# homegreen_node_basic_v1_4_3.net
KiCad netlist of a schematic drawn in EAGLE
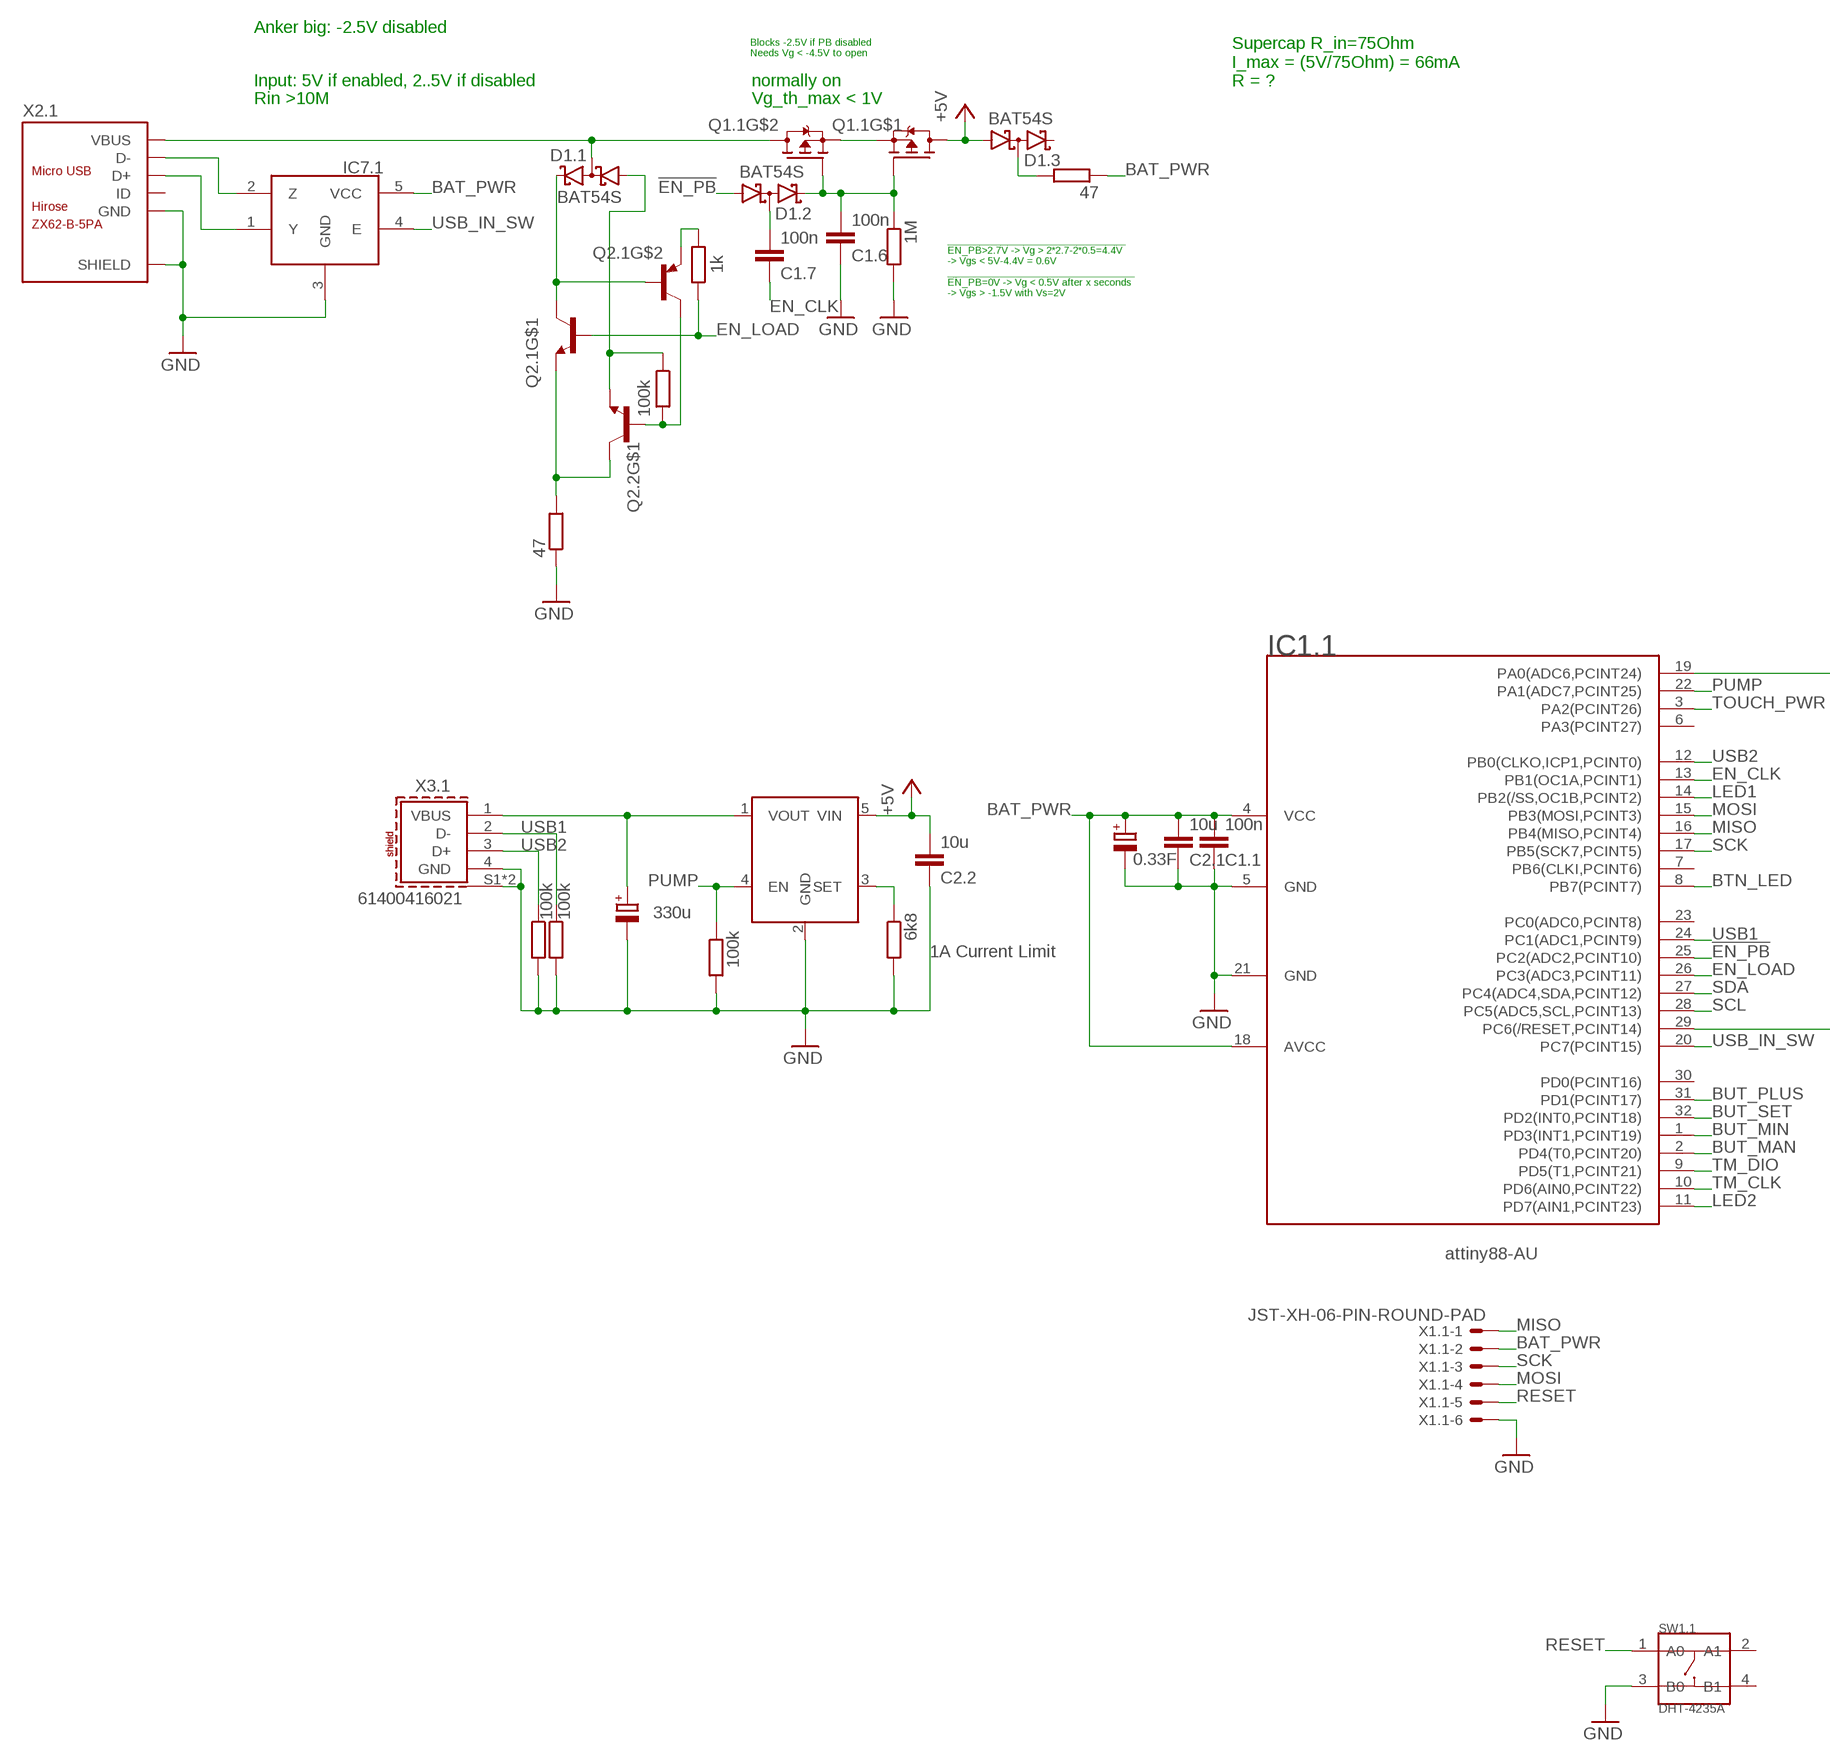
[diagram p0: schematic, sheet 1, part 1 of 2]
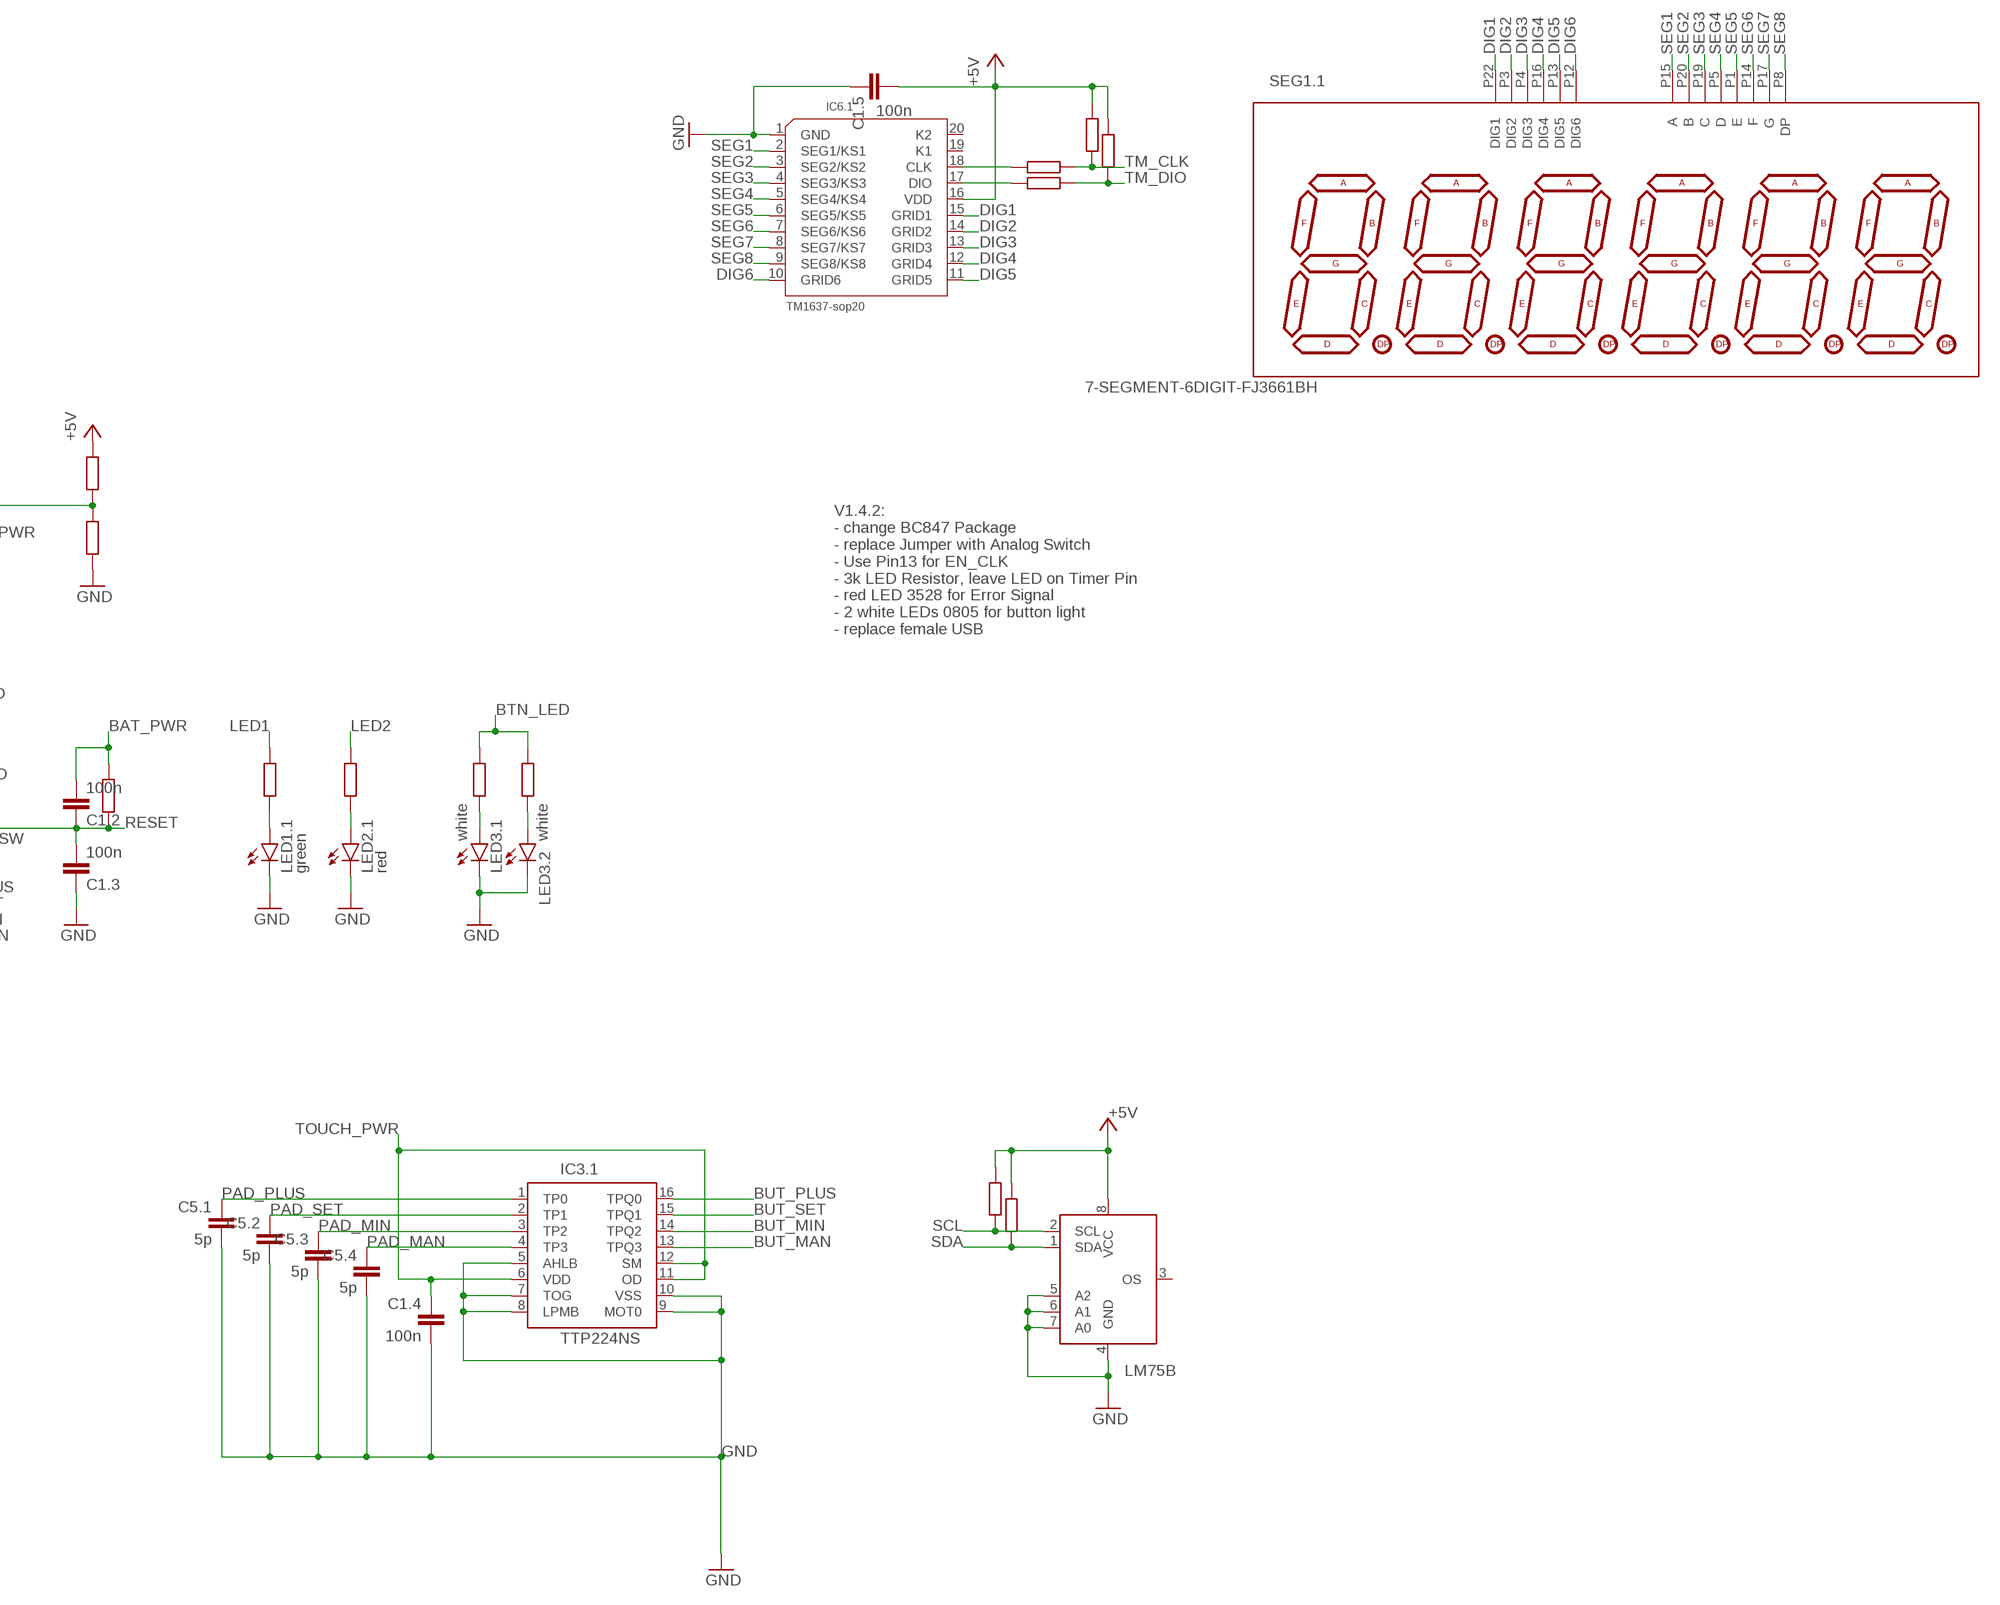
[diagram p1: schematic, sheet 1, part 2 of 2]

(export (version "E")
  (design (tool "Eeschema 10.0.6"))
  (components
    (comp (ref "C1.1")
      (value "100n")
      (footprint "eagle-import:C0805")
      (libsource (lib "eagle-import") (part "C-EUC0805"))
    )
    (comp (ref "C1.2")
      (value "100n")
      (footprint "eagle-import:C0805")
      (libsource (lib "eagle-import") (part "C-EUC0805"))
    )
    (comp (ref "C1.3")
      (value "100n")
      (footprint "eagle-import:C0805")
      (libsource (lib "eagle-import") (part "C-EUC0805"))
    )
    (comp (ref "C1.4")
      (value "100n")
      (footprint "eagle-import:C0805")
      (libsource (lib "eagle-import") (part "C-EUC0805"))
    )
    (comp (ref "C1.5")
      (value "100n")
      (footprint "eagle-import:C0805")
      (libsource (lib "eagle-import") (part "C-EUC0805"))
    )
    (comp (ref "C1.6")
      (value "100n")
      (footprint "eagle-import:C0805")
      (libsource (lib "eagle-import") (part "C-EUC0805"))
    )
    (comp (ref "C1.7")
      (value "100n")
      (footprint "eagle-import:C0805")
      (libsource (lib "eagle-import") (part "C-EUC0805"))
    )
    (comp (ref "C2.1")
      (value "10u")
      (footprint "eagle-import:C0805")
      (libsource (lib "eagle-import") (part "C-EUC0805"))
    )
    (comp (ref "C2.2")
      (value "10u")
      (footprint "eagle-import:C0805")
      (libsource (lib "eagle-import") (part "C-EUC0805"))
    )
    (comp (ref "C3.1")
      (value "0.33F")
      (footprint "eagle-import:C_FYD0H104ZF")
      (libsource (lib "eagle-import") (part "SUPERCAP"))
    )
    (comp (ref "C4.1")
      (value "330u")
      (footprint "eagle-import:PANASONIC_D")
      (libsource (lib "eagle-import") (part "CPOL-EUD"))
    )
    (comp (ref "C5.1")
      (value "5p")
      (footprint "eagle-import:C0805")
      (libsource (lib "eagle-import") (part "C-EUC0805"))
    )
    (comp (ref "C5.2")
      (value "5p")
      (footprint "eagle-import:C0805")
      (libsource (lib "eagle-import") (part "C-EUC0805"))
    )
    (comp (ref "C5.3")
      (value "5p")
      (footprint "eagle-import:C0805")
      (libsource (lib "eagle-import") (part "C-EUC0805"))
    )
    (comp (ref "C5.4")
      (value "5p")
      (footprint "eagle-import:C0805")
      (libsource (lib "eagle-import") (part "C-EUC0805"))
    )
    (comp (ref "D1.1")
      (value "BAT54S")
      (footprint "eagle-import:SOT23")
      (libsource (lib "eagle-import") (part "BAT54S"))
    )
    (comp (ref "D1.2")
      (value "BAT54S")
      (footprint "eagle-import:SOT23")
      (libsource (lib "eagle-import") (part "BAT54S"))
    )
    (comp (ref "D1.3")
      (value "BAT54S")
      (footprint "eagle-import:SOT23")
      (libsource (lib "eagle-import") (part "BAT54S"))
    )
    (comp (ref "IC1.1")
      (value "attiny88-AU")
      (footprint "eagle-import:TQFP32-08")
      (libsource (lib "eagle-import") (part "ATTINY88"))
    )
    (comp (ref "IC2.1")
      (value "LM75B")
      (footprint "eagle-import:SO8")
      (libsource (lib "eagle-import") (part "LM75B"))
    )
    (comp (ref "IC3.1")
      (value "TTP224NS")
      (footprint "eagle-import:SSOP16")
      (libsource (lib "eagle-import") (part "TTP224NS"))
    )
    (comp (ref "IC5.1")
      (value "MT9700_WS4603")
      (footprint "eagle-import:SOT23-5")
      (libsource (lib "eagle-import") (part "MT9700MT9700"))
    )
    (comp (ref "IC6.1")
      (value "TM1637-sop20")
      (footprint "eagle-import:SOP20-1.27-12.7X7.65MM")
      (fields (field (name "MPN") "TM1637"))
      (libsource (lib "eagle-import") (part "DRIVER-TM1637(SOP20)"))
    )
    (comp (ref "IC7.1")
      (value "74AHC1G66")
      (footprint "eagle-import:SOT65P212X110-5N")
      (libsource (lib "eagle-import") (part "74AHC1G66"))
    )
    (comp (ref "LED1.1")
      (value "green")
      (footprint "eagle-import:KA-3528ASYC")
      (libsource (lib "eagle-import") (part "LEDKA-3528ASYC"))
    )
    (comp (ref "LED2.1")
      (value "red")
      (footprint "eagle-import:KA-3528ASYC")
      (libsource (lib "eagle-import") (part "LEDKA-3528ASYC"))
    )
    (comp (ref "LED3.1")
      (value "white")
      (footprint "eagle-import:CHIPLED_0805")
      (libsource (lib "eagle-import") (part "LEDCHIPLED_0805"))
    )
    (comp (ref "LED3.2")
      (value "white")
      (footprint "eagle-import:CHIPLED_0805")
      (libsource (lib "eagle-import") (part "LEDCHIPLED_0805"))
    )
    (comp (ref "Q1.1")
      (value "WST2011")
      (footprint "eagle-import:SOT23-6")
      (libsource (lib "eagle-import") (part "CJL2623SOT23-6"))
    )
    (comp (ref "Q2.1")
      (value "BC817DPN")
      (footprint "eagle-import:SOT23-6")
      (libsource (lib "eagle-import") (part "BC817DPN"))
    )
    (comp (ref "Q2.2")
      (value "BC817DPN")
      (footprint "eagle-import:SOT23-6")
      (libsource (lib "eagle-import") (part "BC817DPN"))
    )
    (comp (ref "R1.1")
      (value "6k8")
      (footprint "eagle-import:R0805")
      (libsource (lib "eagle-import") (part "R-EU_R0805"))
    )
    (comp (ref "R1.2")
      (value "6k8")
      (footprint "eagle-import:R0805")
      (libsource (lib "eagle-import") (part "R-EU_R0805"))
    )
    (comp (ref "R1.3")
      (value "6k8")
      (footprint "eagle-import:R0805")
      (libsource (lib "eagle-import") (part "R-EU_R0805"))
    )
    (comp (ref "R2.1")
      (value "1k")
      (footprint "eagle-import:R0805")
      (libsource (lib "eagle-import") (part "R-EU_R0805"))
    )
    (comp (ref "R2.2")
      (value "1k")
      (footprint "eagle-import:R0805")
      (libsource (lib "eagle-import") (part "R-EU_R0805"))
    )
    (comp (ref "R2.3")
      (value "1k")
      (footprint "eagle-import:R0805")
      (libsource (lib "eagle-import") (part "R-EU_R0805"))
    )
    (comp (ref "R2.4")
      (value "1k")
      (footprint "eagle-import:R0805")
      (libsource (lib "eagle-import") (part "R-EU_R0805"))
    )
    (comp (ref "R2.5")
      (value "1k")
      (footprint "eagle-import:R0805")
      (libsource (lib "eagle-import") (part "R-EU_R0805"))
    )
    (comp (ref "R3.1")
      (value "47")
      (footprint "eagle-import:R0805")
      (libsource (lib "eagle-import") (part "R-EU_R0805"))
    )
    (comp (ref "R3.2")
      (value "47")
      (footprint "eagle-import:R0805")
      (libsource (lib "eagle-import") (part "R-EU_R0805"))
    )
    (comp (ref "R4.1")
      (value "3k")
      (footprint "eagle-import:R0805")
      (libsource (lib "eagle-import") (part "R-EU_R0805"))
    )
    (comp (ref "R4.2")
      (value "3k")
      (footprint "eagle-import:R0805")
      (libsource (lib "eagle-import") (part "R-EU_R0805"))
    )
    (comp (ref "R5.1")
      (value "100k")
      (footprint "eagle-import:R0805")
      (libsource (lib "eagle-import") (part "R-EU_R0805"))
    )
    (comp (ref "R5.2")
      (value "100k")
      (footprint "eagle-import:R0805")
      (libsource (lib "eagle-import") (part "R-EU_R0805"))
    )
    (comp (ref "R5.3")
      (value "100k")
      (footprint "eagle-import:R0805")
      (libsource (lib "eagle-import") (part "R-EU_R0805"))
    )
    (comp (ref "R5.4")
      (value "100k")
      (footprint "eagle-import:R0805")
      (libsource (lib "eagle-import") (part "R-EU_R0805"))
    )
    (comp (ref "R5.5")
      (value "100k")
      (footprint "eagle-import:R0805")
      (libsource (lib "eagle-import") (part "R-EU_R0805"))
    )
    (comp (ref "R5.6")
      (value "100k")
      (footprint "eagle-import:R0805")
      (libsource (lib "eagle-import") (part "R-EU_R0805"))
    )
    (comp (ref "R5.7")
      (value "100k")
      (footprint "eagle-import:R0805")
      (libsource (lib "eagle-import") (part "R-EU_R0805"))
    )
    (comp (ref "R5.8")
      (value "100k")
      (footprint "eagle-import:R0805")
      (libsource (lib "eagle-import") (part "R-EU_R0805"))
    )
    (comp (ref "R5.9")
      (value "100k")
      (footprint "eagle-import:R0805")
      (libsource (lib "eagle-import") (part "R-EU_R0805"))
    )
    (comp (ref "R6.1")
      (value "1M")
      (footprint "eagle-import:R0805")
      (libsource (lib "eagle-import") (part "R-EU_R0805"))
    )
    (comp (ref "SEG1.1")
      (value "7-SEGMENT-6DIGIT-FJ3661BH")
      (footprint "eagle-import:7SEG_6D_FJ3661BH")
      (libsource (lib "eagle-import") (part "7-SEGMENT-6DIGIT-FJ3661BH"))
    )
    (comp (ref "SW1.1")
      (value "DHT-4235A")
      (footprint "eagle-import:SW4-SMD-4.2X3.2X2.5MM")
      (libsource (lib "eagle-import") (part "SMD-BUTTON-TOP-DHT-4235A(4P-4.2X3.2MM)"))
    )
    (comp (ref "X1.1")
      (value "JST-XH-06-PIN-ROUND-PAD")
      (footprint "eagle-import:JST-XH-06-PACKAGE-ROUND-PAD")
      (libsource (lib "eagle-import") (part "JST-XH-06-PIN-ROUND-PAD"))
    )
    (comp (ref "X2.1")
      (value "ZX62-B-5PA")
      (footprint "eagle-import:ZX62-B-5PA")
      (libsource (lib "eagle-import") (part "MICRO-USB-SMD(ZX62-B-5PA)"))
    )
    (comp (ref "X3.1")
      (value "61400416021")
      (footprint "eagle-import:61400416021")
      (libsource (lib "eagle-import") (part "61400416021"))
    )
  )
  (nets
    (net (code "1") (name "+5V") (class "Default")
      (node (ref "C1.5") (pin "2") (pinfunction "2_2") (pintype "passive"))
      (node (ref "C2.2") (pin "2") (pinfunction "2_2") (pintype "passive"))
      (node (ref "D1.3") (pin "1") (pinfunction "A1_1") (pintype "passive"))
      (node (ref "IC2.1") (pin "8") (pinfunction "VCC_8") (pintype "power_in"))
      (node (ref "IC5.1") (pin "5") (pinfunction "VIN_5") (pintype "bidirectional"))
      (node (ref "IC6.1") (pin "16") (pinfunction "VDD_16") (pintype "bidirectional"))
      (node (ref "Q1.1") (pin "6") (pinfunction "D_6") (pintype "passive"))
      (node (ref "R1.1") (pin "2") (pinfunction "2_2") (pintype "passive"))
      (node (ref "R1.3") (pin "2") (pinfunction "2_2") (pintype "passive"))
      (node (ref "R5.3") (pin "1") (pinfunction "1_1") (pintype "passive"))
      (node (ref "R5.5") (pin "2") (pinfunction "2_2") (pintype "passive"))
      (node (ref "R5.6") (pin "2") (pinfunction "2_2") (pintype "passive"))
    )
    (net (code "2") (name "/BAT_PWR") (class "Default")
      (node (ref "C1.1") (pin "2") (pinfunction "2_2") (pintype "passive"))
      (node (ref "C1.2") (pin "2") (pinfunction "2_2") (pintype "passive"))
      (node (ref "C2.1") (pin "2") (pinfunction "2_2") (pintype "passive"))
      (node (ref "C3.1") (pin "+") (pinfunction "+_+") (pintype "passive"))
      (node (ref "IC1.1") (pin "18") (pinfunction "AVCC_18") (pintype "power_in"))
      (node (ref "IC1.1") (pin "4") (pinfunction "VCC_4") (pintype "power_in"))
      (node (ref "IC7.1") (pin "5") (pinfunction "VCC_5") (pintype "bidirectional"))
      (node (ref "R3.2") (pin "1") (pinfunction "1_1") (pintype "passive"))
      (node (ref "R5.7") (pin "1") (pinfunction "1_1") (pintype "passive"))
      (node (ref "X1.1") (pin "2") (pinfunction "S_2") (pintype "passive"))
    )
    (net (code "3") (name "/BTN_LED") (class "Default")
      (node (ref "IC1.1") (pin "8") (pinfunction "PB7(PCINT7)_8") (pintype "bidirectional"))
      (node (ref "R2.1") (pin "2") (pinfunction "2_2") (pintype "passive"))
      (node (ref "R2.5") (pin "2") (pinfunction "2_2") (pintype "passive"))
    )
    (net (code "4") (name "/BUT_MAN") (class "Default")
      (node (ref "IC1.1") (pin "2") (pinfunction "PD4(T0,PCINT20)_2") (pintype "bidirectional"))
      (node (ref "IC3.1") (pin "13") (pinfunction "TPQ3_13") (pintype "bidirectional"))
    )
    (net (code "5") (name "/BUT_MIN") (class "Default")
      (node (ref "IC1.1") (pin "1") (pinfunction "PD3(INT1,PCINT19)_1") (pintype "bidirectional"))
      (node (ref "IC3.1") (pin "14") (pinfunction "TPQ2_14") (pintype "bidirectional"))
    )
    (net (code "6") (name "/BUT_PLUS") (class "Default")
      (node (ref "IC1.1") (pin "31") (pinfunction "PD1(PCINT17)_31") (pintype "bidirectional"))
      (node (ref "IC3.1") (pin "16") (pinfunction "TPQ0_16") (pintype "bidirectional"))
    )
    (net (code "7") (name "/BUT_SET") (class "Default")
      (node (ref "IC1.1") (pin "32") (pinfunction "PD2(INT0,PCINT18)_32") (pintype "bidirectional"))
      (node (ref "IC3.1") (pin "15") (pinfunction "TPQ1_15") (pintype "bidirectional"))
    )
    (net (code "8") (name "/DIG1") (class "Default")
      (node (ref "IC6.1") (pin "15") (pinfunction "GRID1_15") (pintype "bidirectional"))
      (node (ref "SEG1.1") (pin "P22") (pinfunction "DIG1_P22") (pintype "bidirectional"))
    )
    (net (code "9") (name "/DIG2") (class "Default")
      (node (ref "IC6.1") (pin "14") (pinfunction "GRID2_14") (pintype "bidirectional"))
      (node (ref "SEG1.1") (pin "P3") (pinfunction "DIG2_P3") (pintype "bidirectional"))
    )
    (net (code "10") (name "/DIG3") (class "Default")
      (node (ref "IC6.1") (pin "13") (pinfunction "GRID3_13") (pintype "bidirectional"))
      (node (ref "SEG1.1") (pin "P4") (pinfunction "DIG3_P4") (pintype "bidirectional"))
    )
    (net (code "11") (name "/DIG4") (class "Default")
      (node (ref "IC6.1") (pin "12") (pinfunction "GRID4_12") (pintype "bidirectional"))
      (node (ref "SEG1.1") (pin "P16") (pinfunction "DIG4_P16") (pintype "bidirectional"))
    )
    (net (code "12") (name "/DIG5") (class "Default")
      (node (ref "IC6.1") (pin "11") (pinfunction "GRID5_11") (pintype "bidirectional"))
      (node (ref "SEG1.1") (pin "P13") (pinfunction "DIG5_P13") (pintype "bidirectional"))
    )
    (net (code "13") (name "/DIG6") (class "Default")
      (node (ref "IC6.1") (pin "10") (pinfunction "GRID6_10") (pintype "bidirectional"))
      (node (ref "SEG1.1") (pin "P12") (pinfunction "DIG6_P12") (pintype "bidirectional"))
    )
    (net (code "14") (name "/EN_CLK") (class "Default")
      (node (ref "C1.7") (pin "1") (pinfunction "1_1") (pintype "passive"))
      (node (ref "IC1.1") (pin "13") (pinfunction "PB1(OC1A,PCINT1)_13") (pintype "bidirectional"))
    )
    (net (code "15") (name "/EN_LOAD") (class "Default")
      (node (ref "IC1.1") (pin "26") (pinfunction "PC3(ADC3,PCINT11)_26") (pintype "bidirectional"))
      (node (ref "Q2.1") (pin "2") (pinfunction "B_2") (pintype "passive"))
      (node (ref "R2.4") (pin "1") (pinfunction "1_1") (pintype "passive"))
    )
    (net (code "16") (name "/LED1") (class "Default")
      (node (ref "IC1.1") (pin "14") (pinfunction "PB2(/SS,OC1B,PCINT2)_14") (pintype "bidirectional"))
      (node (ref "R4.1") (pin "2") (pinfunction "2_2") (pintype "passive"))
    )
    (net (code "17") (name "/LED2") (class "Default")
      (node (ref "IC1.1") (pin "11") (pinfunction "PD7(AIN1,PCINT23)_11") (pintype "bidirectional"))
      (node (ref "R4.2") (pin "2") (pinfunction "2_2") (pintype "passive"))
    )
    (net (code "18") (name "/MISO") (class "Default")
      (node (ref "IC1.1") (pin "16") (pinfunction "PB4(MISO,PCINT4)_16") (pintype "bidirectional"))
      (node (ref "X1.1") (pin "1") (pinfunction "S_1") (pintype "passive"))
    )
    (net (code "19") (name "/MOSI") (class "Default")
      (node (ref "IC1.1") (pin "15") (pinfunction "PB3(MOSI,PCINT3)_15") (pintype "bidirectional"))
      (node (ref "X1.1") (pin "4") (pinfunction "S_4") (pintype "passive"))
    )
    (net (code "20") (name "/PAD_MAN") (class "Default")
      (node (ref "C5.4") (pin "1") (pinfunction "1_1") (pintype "passive"))
      (node (ref "IC3.1") (pin "4") (pinfunction "TP3_4") (pintype "bidirectional"))
    )
    (net (code "21") (name "/PAD_MIN") (class "Default")
      (node (ref "C5.3") (pin "1") (pinfunction "1_1") (pintype "passive"))
      (node (ref "IC3.1") (pin "3") (pinfunction "TP2_3") (pintype "bidirectional"))
    )
    (net (code "22") (name "/PAD_PLUS") (class "Default")
      (node (ref "C5.1") (pin "1") (pinfunction "1_1") (pintype "passive"))
      (node (ref "IC3.1") (pin "1") (pinfunction "TP0_1") (pintype "bidirectional"))
    )
    (net (code "23") (name "/PAD_SET") (class "Default")
      (node (ref "C5.2") (pin "1") (pinfunction "1_1") (pintype "passive"))
      (node (ref "IC3.1") (pin "2") (pinfunction "TP1_2") (pintype "bidirectional"))
    )
    (net (code "24") (name "/PUMP") (class "Default")
      (node (ref "IC1.1") (pin "22") (pinfunction "PA1(ADC7,PCINT25)_22") (pintype "bidirectional"))
      (node (ref "IC5.1") (pin "4") (pinfunction "EN_4") (pintype "bidirectional"))
      (node (ref "R5.2") (pin "1") (pinfunction "1_1") (pintype "passive"))
    )
    (net (code "25") (name "/RESET") (class "Default")
      (node (ref "C1.2") (pin "1") (pinfunction "1_1") (pintype "passive"))
      (node (ref "C1.3") (pin "2") (pinfunction "2_2") (pintype "passive"))
      (node (ref "IC1.1") (pin "29") (pinfunction "PC6(/RESET,PCINT14)_29") (pintype "bidirectional"))
      (node (ref "R5.7") (pin "2") (pinfunction "2_2") (pintype "passive"))
      (node (ref "SW1.1") (pin "1") (pinfunction "A0_1") (pintype "bidirectional"))
      (node (ref "X1.1") (pin "5") (pinfunction "S_5") (pintype "passive"))
    )
    (net (code "26") (name "/SCK") (class "Default")
      (node (ref "IC1.1") (pin "17") (pinfunction "PB5(SCK7,PCINT5)_17") (pintype "bidirectional"))
      (node (ref "X1.1") (pin "3") (pinfunction "S_3") (pintype "passive"))
    )
    (net (code "27") (name "/SCL") (class "Default")
      (node (ref "IC1.1") (pin "28") (pinfunction "PC5(ADC5,SCL,PCINT13)_28") (pintype "bidirectional"))
      (node (ref "IC2.1") (pin "2") (pinfunction "SCL_2") (pintype "bidirectional"))
      (node (ref "R1.3") (pin "1") (pinfunction "1_1") (pintype "passive"))
    )
    (net (code "28") (name "/SDA") (class "Default")
      (node (ref "IC1.1") (pin "27") (pinfunction "PC4(ADC4,SDA,PCINT12)_27") (pintype "bidirectional"))
      (node (ref "IC2.1") (pin "1") (pinfunction "SDA_1") (pintype "bidirectional"))
      (node (ref "R1.1") (pin "1") (pinfunction "1_1") (pintype "passive"))
    )
    (net (code "29") (name "/SEG1") (class "Default")
      (node (ref "IC6.1") (pin "2") (pinfunction "SEG1/KS1_2") (pintype "bidirectional"))
      (node (ref "SEG1.1") (pin "P15") (pinfunction "A_P15") (pintype "bidirectional"))
    )
    (net (code "30") (name "/SEG2") (class "Default")
      (node (ref "IC6.1") (pin "3") (pinfunction "SEG2/KS2_3") (pintype "bidirectional"))
      (node (ref "SEG1.1") (pin "P20") (pinfunction "B_P20") (pintype "bidirectional"))
    )
    (net (code "31") (name "/SEG3") (class "Default")
      (node (ref "IC6.1") (pin "4") (pinfunction "SEG3/KS3_4") (pintype "bidirectional"))
      (node (ref "SEG1.1") (pin "P19") (pinfunction "C_P19") (pintype "bidirectional"))
    )
    (net (code "32") (name "/SEG4") (class "Default")
      (node (ref "IC6.1") (pin "5") (pinfunction "SEG4/KS4_5") (pintype "bidirectional"))
      (node (ref "SEG1.1") (pin "P5") (pinfunction "D_P5") (pintype "bidirectional"))
    )
    (net (code "33") (name "/SEG5") (class "Default")
      (node (ref "IC6.1") (pin "6") (pinfunction "SEG5/KS5_6") (pintype "bidirectional"))
      (node (ref "SEG1.1") (pin "P1") (pinfunction "E_P1") (pintype "bidirectional"))
    )
    (net (code "34") (name "/SEG6") (class "Default")
      (node (ref "IC6.1") (pin "7") (pinfunction "SEG6/KS6_7") (pintype "bidirectional"))
      (node (ref "SEG1.1") (pin "P14") (pinfunction "F_P14") (pintype "bidirectional"))
    )
    (net (code "35") (name "/SEG7") (class "Default")
      (node (ref "IC6.1") (pin "8") (pinfunction "SEG7/KS7_8") (pintype "bidirectional"))
      (node (ref "SEG1.1") (pin "P17") (pinfunction "G_P17") (pintype "bidirectional"))
    )
    (net (code "36") (name "/SEG8") (class "Default")
      (node (ref "IC6.1") (pin "9") (pinfunction "SEG8/KS8_9") (pintype "bidirectional"))
      (node (ref "SEG1.1") (pin "P8") (pinfunction "DP_P8") (pintype "bidirectional"))
    )
    (net (code "37") (name "/TM_CLK") (class "Default")
      (node (ref "IC1.1") (pin "10") (pinfunction "PD6(AIN0,PCINT22)_10") (pintype "bidirectional"))
      (node (ref "R2.2") (pin "1") (pinfunction "1_1") (pintype "passive"))
      (node (ref "R5.5") (pin "1") (pinfunction "1_1") (pintype "passive"))
    )
    (net (code "38") (name "/TM_DIO") (class "Default")
      (node (ref "IC1.1") (pin "9") (pinfunction "PD5(T1,PCINT21)_9") (pintype "bidirectional"))
      (node (ref "R2.3") (pin "1") (pinfunction "1_1") (pintype "passive"))
      (node (ref "R5.6") (pin "1") (pinfunction "1_1") (pintype "passive"))
    )
    (net (code "39") (name "/TOUCH_PWR") (class "Default")
      (node (ref "C1.4") (pin "1") (pinfunction "1_1") (pintype "passive"))
      (node (ref "IC1.1") (pin "3") (pinfunction "PA2(PCINT26)_3") (pintype "bidirectional"))
      (node (ref "IC3.1") (pin "11") (pinfunction "OD_11") (pintype "bidirectional"))
      (node (ref "IC3.1") (pin "12") (pinfunction "SM_12") (pintype "bidirectional"))
      (node (ref "IC3.1") (pin "6") (pinfunction "VDD_6") (pintype "power_in"))
    )
    (net (code "40") (name "/USB1") (class "Default")
      (node (ref "IC1.1") (pin "24") (pinfunction "PC1(ADC1,PCINT9)_24") (pintype "bidirectional"))
      (node (ref "R5.9") (pin "1") (pinfunction "1_1") (pintype "passive"))
      (node (ref "X3.1") (pin "2") (pinfunction "D-_2") (pintype "bidirectional"))
    )
    (net (code "41") (name "/USB2") (class "Default")
      (node (ref "IC1.1") (pin "12") (pinfunction "PB0(CLKO,ICP1,PCINT0)_12") (pintype "bidirectional"))
      (node (ref "R5.8") (pin "1") (pinfunction "1_1") (pintype "passive"))
      (node (ref "X3.1") (pin "3") (pinfunction "D+_3") (pintype "bidirectional"))
    )
    (net (code "42") (name "/USB_IN_SW") (class "Default")
      (node (ref "IC1.1") (pin "20") (pinfunction "PC7(PCINT15)_20") (pintype "bidirectional"))
      (node (ref "IC7.1") (pin "4") (pinfunction "E_4") (pintype "bidirectional"))
    )
    (net (code "43") (name "/~{EN_PB}") (class "Default")
      (node (ref "D1.2") (pin "1") (pinfunction "A1_1") (pintype "passive"))
      (node (ref "IC1.1") (pin "25") (pinfunction "PC2(ADC2,PCINT10)_25") (pintype "bidirectional"))
    )
    (net (code "44") (name "GND") (class "Default")
      (node (ref "C1.1") (pin "1") (pinfunction "1_1") (pintype "passive"))
      (node (ref "C1.3") (pin "1") (pinfunction "1_1") (pintype "passive"))
      (node (ref "C1.4") (pin "2") (pinfunction "2_2") (pintype "passive"))
      (node (ref "C1.5") (pin "1") (pinfunction "1_1") (pintype "passive"))
      (node (ref "C1.6") (pin "1") (pinfunction "1_1") (pintype "passive"))
      (node (ref "C2.1") (pin "1") (pinfunction "1_1") (pintype "passive"))
      (node (ref "C2.2") (pin "1") (pinfunction "1_1") (pintype "passive"))
      (node (ref "C3.1") (pin "-") (pinfunction "-_-") (pintype "passive"))
      (node (ref "C4.1") (pin "-") (pinfunction "-_-") (pintype "passive"))
      (node (ref "C5.1") (pin "2") (pinfunction "2_2") (pintype "passive"))
      (node (ref "C5.2") (pin "2") (pinfunction "2_2") (pintype "passive"))
      (node (ref "C5.3") (pin "2") (pinfunction "2_2") (pintype "passive"))
      (node (ref "C5.4") (pin "2") (pinfunction "2_2") (pintype "passive"))
      (node (ref "IC1.1") (pin "21") (pinfunction "GND_21") (pintype "power_in"))
      (node (ref "IC1.1") (pin "5") (pinfunction "GND_5") (pintype "power_in"))
      (node (ref "IC2.1") (pin "4") (pinfunction "GND_4") (pintype "bidirectional"))
      (node (ref "IC2.1") (pin "5") (pinfunction "A2_5") (pintype "input"))
      (node (ref "IC2.1") (pin "6") (pinfunction "A1_6") (pintype "input"))
      (node (ref "IC2.1") (pin "7") (pinfunction "A0_7") (pintype "input"))
      (node (ref "IC3.1") (pin "10") (pinfunction "VSS_10") (pintype "power_in"))
      (node (ref "IC3.1") (pin "5") (pinfunction "AHLB_5") (pintype "bidirectional"))
      (node (ref "IC3.1") (pin "7") (pinfunction "TOG_7") (pintype "bidirectional"))
      (node (ref "IC3.1") (pin "8") (pinfunction "LPMB_8") (pintype "bidirectional"))
      (node (ref "IC3.1") (pin "9") (pinfunction "MOT0_9") (pintype "bidirectional"))
      (node (ref "IC5.1") (pin "2") (pinfunction "GND_2") (pintype "bidirectional"))
      (node (ref "IC6.1") (pin "1") (pinfunction "GND_1") (pintype "bidirectional"))
      (node (ref "IC7.1") (pin "3") (pinfunction "GND_3") (pintype "bidirectional"))
      (node (ref "LED1.1") (pin "C") (pinfunction "C_C") (pintype "passive"))
      (node (ref "LED2.1") (pin "C") (pinfunction "C_C") (pintype "passive"))
      (node (ref "LED3.1") (pin "C") (pinfunction "C_C") (pintype "passive"))
      (node (ref "LED3.2") (pin "C") (pinfunction "C_C") (pintype "passive"))
      (node (ref "R1.2") (pin "2") (pinfunction "2_2") (pintype "passive"))
      (node (ref "R3.1") (pin "1") (pinfunction "1_1") (pintype "passive"))
      (node (ref "R5.2") (pin "2") (pinfunction "2_2") (pintype "passive"))
      (node (ref "R5.4") (pin "2") (pinfunction "2_2") (pintype "passive"))
      (node (ref "R5.8") (pin "2") (pinfunction "2_2") (pintype "passive"))
      (node (ref "R5.9") (pin "2") (pinfunction "2_2") (pintype "passive"))
      (node (ref "R6.1") (pin "2") (pinfunction "2_2") (pintype "passive"))
      (node (ref "SW1.1") (pin "3") (pinfunction "B0_3") (pintype "bidirectional"))
      (node (ref "X1.1") (pin "6") (pinfunction "S_6") (pintype "passive"))
      (node (ref "X2.1") (pin "5") (pinfunction "GND_5") (pintype "power_in"))
      (node (ref "X2.1") (pin "P1") (pinfunction "SHIELD_P1") (pintype "power_in"))
      (node (ref "X2.1") (pin "P2") (pinfunction "SHIELD_P2") (pintype "power_in"))
      (node (ref "X2.1") (pin "P3") (pinfunction "SHIELD_P3") (pintype "power_in"))
      (node (ref "X2.1") (pin "P4") (pinfunction "SHIELD_P4") (pintype "power_in"))
      (node (ref "X2.1") (pin "P5") (pinfunction "SHIELD_P5") (pintype "power_in"))
      (node (ref "X2.1") (pin "P6") (pinfunction "SHIELD_P6") (pintype "power_in"))
      (node (ref "X3.1") (pin "4") (pinfunction "GND_4") (pintype "bidirectional"))
      (node (ref "X3.1") (pin "S1") (pinfunction "SHIELD_S1") (pintype "bidirectional"))
      (node (ref "X3.1") (pin "S2") (pinfunction "SHIELD_S2") (pintype "bidirectional"))
    )
    (net (code "45") (name "Net-(D1.1-A1)") (class "Default")
      (node (ref "D1.1") (pin "1") (pinfunction "A1_1") (pintype "passive"))
      (node (ref "Q2.2") (pin "1") (pinfunction "E_1") (pintype "passive"))
      (node (ref "R5.1") (pin "1") (pinfunction "1_1") (pintype "passive"))
    )
    (net (code "46") (name "Net-(D1.1-C1A2)") (class "Default")
      (node (ref "D1.1") (pin "3") (pinfunction "C1A2_3") (pintype "passive"))
      (node (ref "Q1.1") (pin "4") (pinfunction "D_4") (pintype "passive"))
      (node (ref "X2.1") (pin "1") (pinfunction "VBUS_1") (pintype "power_in"))
    )
    (net (code "47") (name "Net-(D1.1-C2)") (class "Default")
      (node (ref "D1.1") (pin "2") (pinfunction "C2_2") (pintype "passive"))
      (node (ref "Q2.1") (pin "5") (pinfunction "B_5") (pintype "passive"))
      (node (ref "Q2.1") (pin "6") (pinfunction "C_6") (pintype "passive"))
    )
    (net (code "48") (name "Net-(D1.2-C1A2)") (class "Default")
      (node (ref "C1.7") (pin "2") (pinfunction "2_2") (pintype "passive"))
      (node (ref "D1.2") (pin "3") (pinfunction "C1A2_3") (pintype "passive"))
    )
    (net (code "49") (name "Net-(D1.2-C2)") (class "Default")
      (node (ref "C1.6") (pin "2") (pinfunction "2_2") (pintype "passive"))
      (node (ref "D1.2") (pin "2") (pinfunction "C2_2") (pintype "passive"))
      (node (ref "Q1.1") (pin "1") (pinfunction "G_1") (pintype "passive"))
      (node (ref "Q1.1") (pin "3") (pinfunction "G_3") (pintype "passive"))
      (node (ref "R6.1") (pin "1") (pinfunction "1_1") (pintype "passive"))
    )
    (net (code "50") (name "Net-(D1.3-C1A2)") (class "Default")
      (node (ref "D1.3") (pin "3") (pinfunction "C1A2_3") (pintype "passive"))
      (node (ref "R3.2") (pin "2") (pinfunction "2_2") (pintype "passive"))
    )
    (net (code "51") (name "Net-(IC1.1-PA0(ADC6,PCINT24))") (class "Default")
      (node (ref "IC1.1") (pin "19") (pinfunction "PA0(ADC6,PCINT24)_19") (pintype "bidirectional"))
      (node (ref "R5.3") (pin "2") (pinfunction "2_2") (pintype "passive"))
      (node (ref "R5.4") (pin "1") (pinfunction "1_1") (pintype "passive"))
    )
    (net (code "52") (name "Net-(IC5.1-SET)") (class "Default")
      (node (ref "IC5.1") (pin "3") (pinfunction "SET_3") (pintype "bidirectional"))
      (node (ref "R1.2") (pin "1") (pinfunction "1_1") (pintype "passive"))
    )
    (net (code "53") (name "Net-(IC5.1-VOUT)") (class "Default")
      (node (ref "C4.1") (pin "+") (pinfunction "+_+") (pintype "passive"))
      (node (ref "IC5.1") (pin "1") (pinfunction "VOUT_1") (pintype "bidirectional"))
      (node (ref "X3.1") (pin "1") (pinfunction "VBUS_1") (pintype "bidirectional"))
    )
    (net (code "54") (name "Net-(IC6.1-CLK)") (class "Default")
      (node (ref "IC6.1") (pin "18") (pinfunction "CLK_18") (pintype "bidirectional"))
      (node (ref "R2.2") (pin "2") (pinfunction "2_2") (pintype "passive"))
    )
    (net (code "55") (name "Net-(IC6.1-DIO)") (class "Default")
      (node (ref "IC6.1") (pin "17") (pinfunction "DIO_17") (pintype "bidirectional"))
      (node (ref "R2.3") (pin "2") (pinfunction "2_2") (pintype "passive"))
    )
    (net (code "56") (name "Net-(IC7.1-Y)") (class "Default")
      (node (ref "IC7.1") (pin "1") (pinfunction "Y_1") (pintype "bidirectional"))
      (node (ref "X2.1") (pin "3") (pinfunction "D+_3") (pintype "bidirectional"))
    )
    (net (code "57") (name "Net-(IC7.1-Z)") (class "Default")
      (node (ref "IC7.1") (pin "2") (pinfunction "Z_2") (pintype "bidirectional"))
      (node (ref "X2.1") (pin "2") (pinfunction "D-_2") (pintype "bidirectional"))
    )
    (net (code "58") (name "Net-(LED1.1-PadA)") (class "Default")
      (node (ref "LED1.1") (pin "A") (pinfunction "A_A") (pintype "passive"))
      (node (ref "R4.1") (pin "1") (pinfunction "1_1") (pintype "passive"))
    )
    (net (code "59") (name "Net-(LED2.1-PadA)") (class "Default")
      (node (ref "LED2.1") (pin "A") (pinfunction "A_A") (pintype "passive"))
      (node (ref "R4.2") (pin "1") (pinfunction "1_1") (pintype "passive"))
    )
    (net (code "60") (name "Net-(LED3.1-PadA)") (class "Default")
      (node (ref "LED3.1") (pin "A") (pinfunction "A_A") (pintype "passive"))
      (node (ref "R2.1") (pin "1") (pinfunction "1_1") (pintype "passive"))
    )
    (net (code "61") (name "Net-(LED3.2-PadA)") (class "Default")
      (node (ref "LED3.2") (pin "A") (pinfunction "A_A") (pintype "passive"))
      (node (ref "R2.5") (pin "1") (pinfunction "1_1") (pintype "passive"))
    )
    (net (code "62") (name "Net-(Q1.1A-S)") (class "Default")
      (node (ref "Q1.1") (pin "2") (pinfunction "S_2") (pintype "passive"))
      (node (ref "Q1.1") (pin "5") (pinfunction "S_5") (pintype "passive"))
    )
    (net (code "63") (name "Net-(Q2.1A-E)") (class "Default")
      (node (ref "Q2.1") (pin "1") (pinfunction "E_1") (pintype "passive"))
      (node (ref "Q2.2") (pin "6") (pinfunction "C_6") (pintype "passive"))
      (node (ref "R3.1") (pin "2") (pinfunction "2_2") (pintype "passive"))
    )
    (net (code "64") (name "Net-(Q2.1B-C)") (class "Default")
      (node (ref "Q2.1") (pin "3") (pinfunction "C_3") (pintype "passive"))
      (node (ref "Q2.2") (pin "2") (pinfunction "B_2") (pintype "passive"))
      (node (ref "R5.1") (pin "2") (pinfunction "2_2") (pintype "passive"))
    )
    (net (code "65") (name "Net-(Q2.1B-E)") (class "Default")
      (node (ref "Q2.1") (pin "4") (pinfunction "E_4") (pintype "passive"))
      (node (ref "R2.4") (pin "2") (pinfunction "2_2") (pintype "passive"))
    )
    (net (code "66") (name "unconnected-(D1.3-C2-Pad2)") (class "Default")
      (node (ref "D1.3") (pin "2") (pinfunction "C2_2") (pintype "passive"))
    )
    (net (code "67") (name "unconnected-(IC1.1-PA3(PCINT27)-Pad6)") (class "Default")
      (node (ref "IC1.1") (pin "6") (pinfunction "PA3(PCINT27)_6") (pintype "bidirectional"))
    )
    (net (code "68") (name "unconnected-(IC1.1-PB6(CLKI,PCINT6)-Pad7)") (class "Default")
      (node (ref "IC1.1") (pin "7") (pinfunction "PB6(CLKI,PCINT6)_7") (pintype "bidirectional"))
    )
    (net (code "69") (name "unconnected-(IC1.1-PC0(ADC0,PCINT8)-Pad23)") (class "Default")
      (node (ref "IC1.1") (pin "23") (pinfunction "PC0(ADC0,PCINT8)_23") (pintype "bidirectional"))
    )
    (net (code "70") (name "unconnected-(IC1.1-PD0(PCINT16)-Pad30)") (class "Default")
      (node (ref "IC1.1") (pin "30") (pinfunction "PD0(PCINT16)_30") (pintype "bidirectional"))
    )
    (net (code "71") (name "unconnected-(IC2.1-OS-Pad3)") (class "Default")
      (node (ref "IC2.1") (pin "3") (pinfunction "OS_3") (pintype "output"))
    )
    (net (code "72") (name "unconnected-(IC6.1-K1-Pad19)") (class "Default")
      (node (ref "IC6.1") (pin "19") (pinfunction "K1_19") (pintype "bidirectional"))
    )
    (net (code "73") (name "unconnected-(IC6.1-K2-Pad20)") (class "Default")
      (node (ref "IC6.1") (pin "20") (pinfunction "K2_20") (pintype "bidirectional"))
    )
    (net (code "74") (name "unconnected-(SW1.1-A1-Pad2)") (class "Default")
      (node (ref "SW1.1") (pin "2") (pinfunction "A1_2") (pintype "bidirectional"))
    )
    (net (code "75") (name "unconnected-(SW1.1-B1-Pad4)") (class "Default")
      (node (ref "SW1.1") (pin "4") (pinfunction "B1_4") (pintype "bidirectional"))
    )
    (net (code "76") (name "unconnected-(X2.1-ID-Pad4)") (class "Default")
      (node (ref "X2.1") (pin "4") (pinfunction "ID_4") (pintype "bidirectional"))
    )
  )
)
